# OptocouplerKicker.net
KiCad netlist of a schematic drawn in Altium Designer
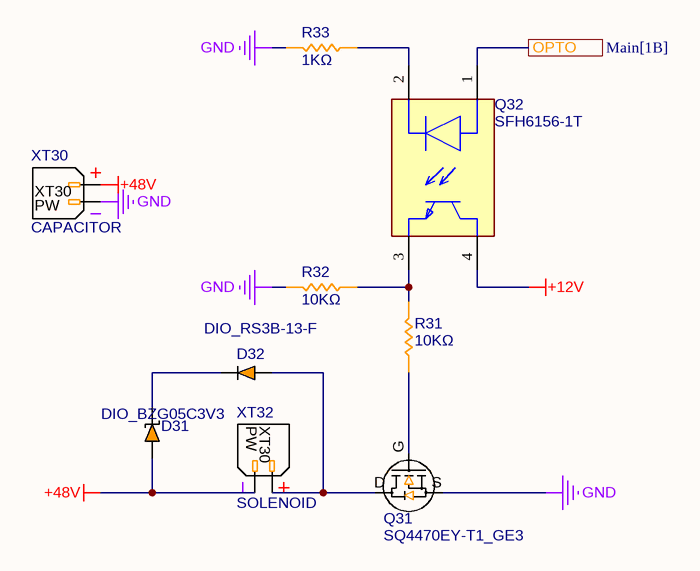
[diagram p0: OptocouplerKicker.SchDoc]

(export (version "E")
  (design (tool "Eeschema 10.0.6"))
  (components
    (comp (ref "D31")
      (value "DIO_BZG05C3V3")
      (footprint "DIO_BZG05C3V3")
      (libsource (lib "GenericRC") (part "DIO_BZG05C3V3"))
    )
    (comp (ref "D32")
      (value "DIO_RS3B-13-F")
      (footprint "DIO_RS3B-13-F")
      (libsource (lib "GenericRC") (part "DIO_RS3B-13-F"))
    )
    (comp (ref "Q31")
      (value "SQ4470EY-T1_GE3")
      (footprint "SQ4470EY-T1_GE3")
      (libsource (lib "RC") (part "SQ4470EY-T1_GE3"))
    )
    (comp (ref "Q32")
      (value "SFH6156-1T")
      (footprint "FP-83911-MFG")
      (description "SFH6156-1T Optocoupler Dc-in 1-CH Transistor Dc-out 4-PIN PDIP SMD T/r")
      (libsource (lib "Altium Content Vault") (part "f2b4bc14f88b93712c96e31096f5e9d"))
    )
    (comp (ref "R31")
      (value "10KΩ")
      (footprint "RES_0603")
      (description "Resistor SMD 0603 generic")
      (libsource (lib "GenericRC") (part "RES_0603"))
    )
    (comp (ref "R32")
      (value "10KΩ")
      (footprint "RES_0603")
      (description "Resistor SMD 0603 generic")
      (libsource (lib "GenericRC") (part "RES_0603"))
    )
    (comp (ref "R33")
      (value "1KΩ")
      (footprint "RES_0603")
      (description "Resistor SMD 0603 generic")
      (libsource (lib "GenericRC") (part "RES_0603"))
    )
    (comp (ref "XT30")
      (value "CAPACITOR")
      (footprint "XT30_PW_M")
      (libsource (lib "GenericRC") (part "XT30_PW_M"))
    )
    (comp (ref "XT32") (value "SOLENOID") (footprint "XT30_PW_M") (libsource (lib "") (part "XT30_PW_M_1")))
  )
  (nets
    (net (code "1") (name "+12V") (class "Default")
      (node (ref "Q32") (pin "4") (pinfunction "C_4") (pintype "passive"))
    )
    (net (code "2") (name "+48V") (class "Default")
      (node (ref "D31") (pin "A") (pintype "passive"))
      (node (ref "XT30") (pin "P") (pinfunction "P_P") (pintype "power_in"))
      (node (ref "XT32") (pin "N") (pinfunction "N_N") (pintype "power_in"))
    )
    (net (code "3") (name "/OPTO") (class "Default")
      (node (ref "Q32") (pin "1") (pinfunction "A_1") (pintype "passive"))
    )
    (net (code "4") (name "GND") (class "Default")
      (node (ref "Q31") (pin "S") (pinfunction "3_S") (pintype "passive"))
      (node (ref "R32") (pin "1") (pintype "passive"))
      (node (ref "R33") (pin "1") (pintype "passive"))
      (node (ref "XT30") (pin "N") (pinfunction "N_N") (pintype "power_in"))
    )
    (net (code "5") (name "Net-(D31-PadC)") (class "Default")
      (node (ref "D31") (pin "C") (pintype "passive"))
      (node (ref "D32") (pin "C") (pintype "passive"))
    )
    (net (code "6") (name "Net-(Q31-4)") (class "Default")
      (node (ref "Q31") (pin "G") (pinfunction "4_G") (pintype "passive"))
      (node (ref "R31") (pin "2") (pintype "passive"))
    )
    (net (code "7") (name "Net-(Q31-5)") (class "Default")
      (node (ref "D32") (pin "A") (pintype "passive"))
      (node (ref "Q31") (pin "D") (pinfunction "5_D") (pintype "passive"))
      (node (ref "XT32") (pin "P") (pinfunction "P_P") (pintype "power_in"))
    )
    (net (code "8") (name "Net-(Q32-C-Pad2)") (class "Default")
      (node (ref "Q32") (pin "2") (pinfunction "C_2") (pintype "passive"))
      (node (ref "R33") (pin "2") (pintype "passive"))
    )
    (net (code "9") (name "Net-(Q32-E)") (class "Default")
      (node (ref "Q32") (pin "3") (pinfunction "E_3") (pintype "passive"))
      (node (ref "R31") (pin "1") (pintype "passive"))
      (node (ref "R32") (pin "2") (pintype "passive"))
    )
  )
)
